# STRWHL-S01-V00-SteeringWheel.net
KiCad netlist of a schematic drawn in Altium Designer
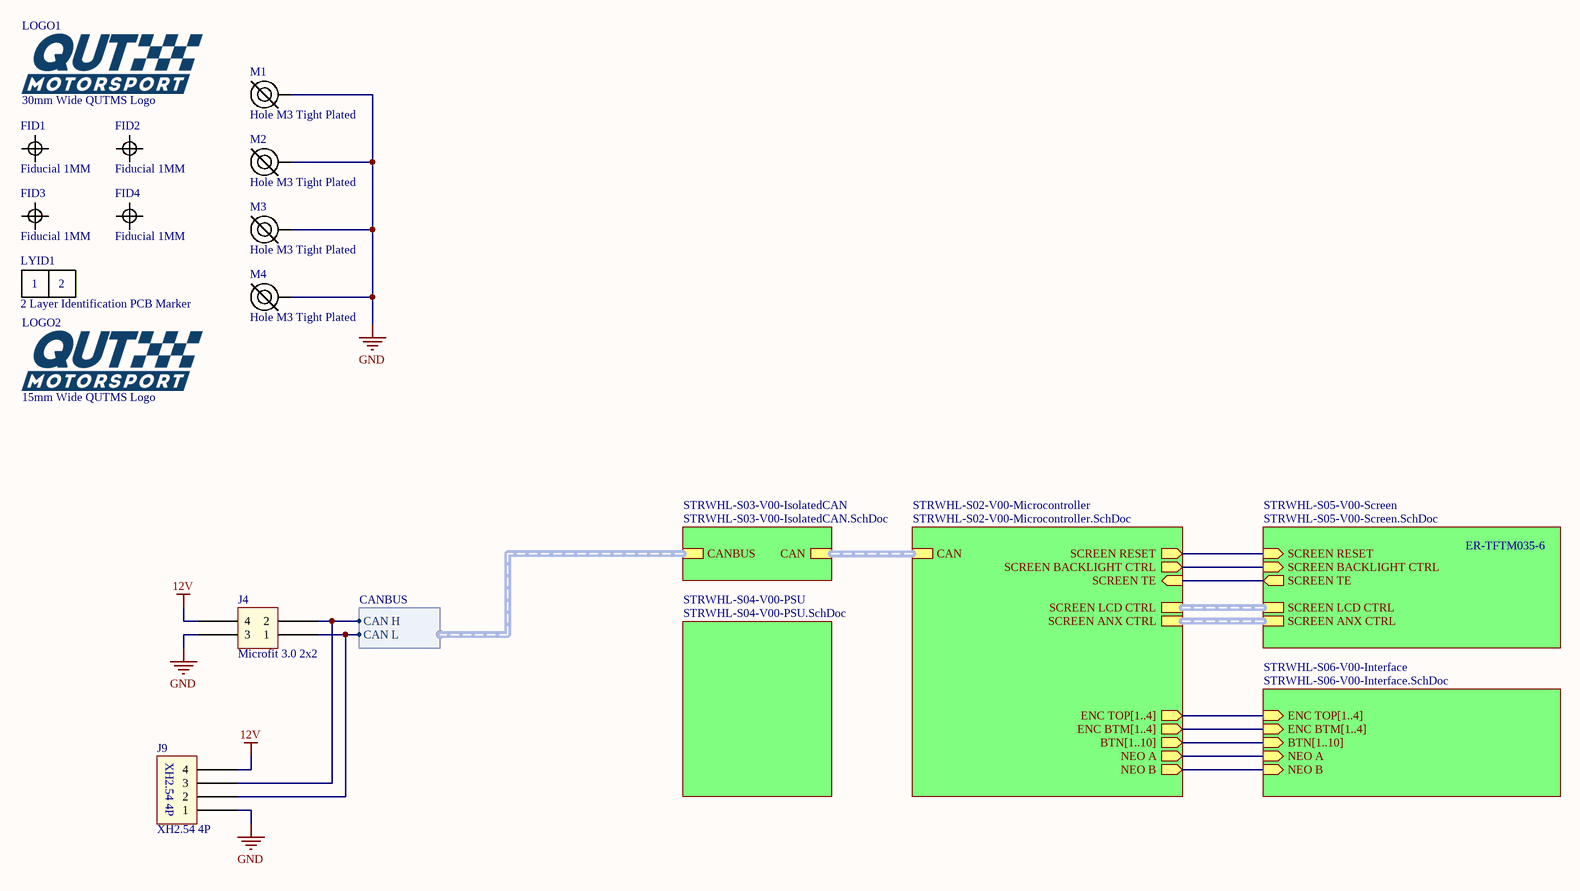
[diagram p0: STRWHL-S01-V00-SteeringWheel.SchDoc]

(export (version "E")
  (design (tool "Eeschema 10.0.6"))
  (components
    (comp (ref "FID1")
      (value "Fiducial 1MM")
      (footprint "FIDUCIAL 1MM")
      (libsource (lib "QUTMS_PCBLibrary") (part "Fiducial 1MM"))
    )
    (comp (ref "FID2")
      (value "Fiducial 1MM")
      (footprint "FIDUCIAL 1MM")
      (libsource (lib "QUTMS_PCBLibrary") (part "Fiducial 1MM"))
    )
    (comp (ref "FID3")
      (value "Fiducial 1MM")
      (footprint "FIDUCIAL 1MM")
      (libsource (lib "QUTMS_PCBLibrary") (part "Fiducial 1MM"))
    )
    (comp (ref "FID4")
      (value "Fiducial 1MM")
      (footprint "FIDUCIAL 1MM")
      (libsource (lib "QUTMS_PCBLibrary") (part "Fiducial 1MM"))
    )
    (comp (ref "J4")
      (value "Microfit 3.0 2x2")
      (footprint "Microfit_2X2_R_TH")
      (libsource (lib "QUTMS_MicrofitLibrary") (part "Microfit_2x2"))
    )
    (comp (ref "J9")
      (value "XH2.54 4P")
      (footprint "JST_XH254_4P_TH_RH")
      (libsource (lib "JST_XH254") (part "XH2.54 4P"))
    )
    (comp (ref "LOGO1")
      (value "30mm Wide QUTMS Logo")
      (footprint "QUTMS LOGO 30MM")
      (libsource (lib "QUTMS_PCBLibrary") (part "QUTMS Logo 30mm"))
    )
    (comp (ref "LOGO2")
      (value "15mm Wide QUTMS Logo")
      (footprint "QUTMS LOGO 15MM")
      (libsource (lib "QUTMS_PCBLibrary") (part "QUTMS Logo 15mm"))
    )
    (comp (ref "LYID1")
      (value "2 Layer Identification PCB Marker")
      (footprint "LAYER IDENT 2")
      (libsource (lib "QUTMS_PCBLibrary") (part "Layer Identification 2"))
    )
    (comp (ref "M1")
      (value "Hole M3 Tight Plated")
      (footprint "M3.2 PLATED")
      (description "M3.2 Hole, Plated")
      (libsource (lib "QUTMS_PCBLibrary") (part "Hole M3 Tight Plated"))
    )
    (comp (ref "M2")
      (value "Hole M3 Tight Plated")
      (footprint "M3.2 PLATED")
      (description "M3.2 Hole, Plated")
      (libsource (lib "QUTMS_PCBLibrary") (part "Hole M3 Tight Plated"))
    )
    (comp (ref "M3")
      (value "Hole M3 Tight Plated")
      (footprint "M3.2 PLATED")
      (description "M3.2 Hole, Plated")
      (libsource (lib "QUTMS_PCBLibrary") (part "Hole M3 Tight Plated"))
    )
    (comp (ref "M4")
      (value "Hole M3 Tight Plated")
      (footprint "M3.2 PLATED")
      (description "M3.2 Hole, Plated")
      (libsource (lib "QUTMS_PCBLibrary") (part "Hole M3 Tight Plated"))
    )
  )
  (nets
    (net (code "14") (name "12V") (class "Default")
      (node (ref "J4") (pin "4") (pinfunction "4_4") (pintype "passive"))
      (node (ref "J9") (pin "4") (pinfunction "4_4") (pintype "passive"))
    )
    (net (code "15") (name "GND") (class "Default")
      (node (ref "J4") (pin "3") (pinfunction "3_3") (pintype "passive"))
      (node (ref "J9") (pin "1") (pinfunction "1_1") (pintype "passive"))
      (node (ref "M1") (pin "1") (pinfunction "1_1") (pintype "passive"))
      (node (ref "M2") (pin "1") (pinfunction "1_1") (pintype "passive"))
      (node (ref "M3") (pin "1") (pinfunction "1_1") (pintype "passive"))
      (node (ref "M4") (pin "1") (pinfunction "1_1") (pintype "passive"))
    )
    (net (code "16") (name "Net-(J4-Pad1)") (class "Default")
      (node (ref "J4") (pin "1") (pinfunction "1_1") (pintype "passive"))
      (node (ref "J9") (pin "2") (pinfunction "2_2") (pintype "passive"))
    )
    (net (code "17") (name "Net-(J4-Pad2)") (class "Default")
      (node (ref "J4") (pin "2") (pinfunction "2_2") (pintype "passive"))
      (node (ref "J9") (pin "3") (pinfunction "3_3") (pintype "passive"))
    )
  )
)
